# Margay.net
KiCad netlist of a schematic drawn in EAGLE
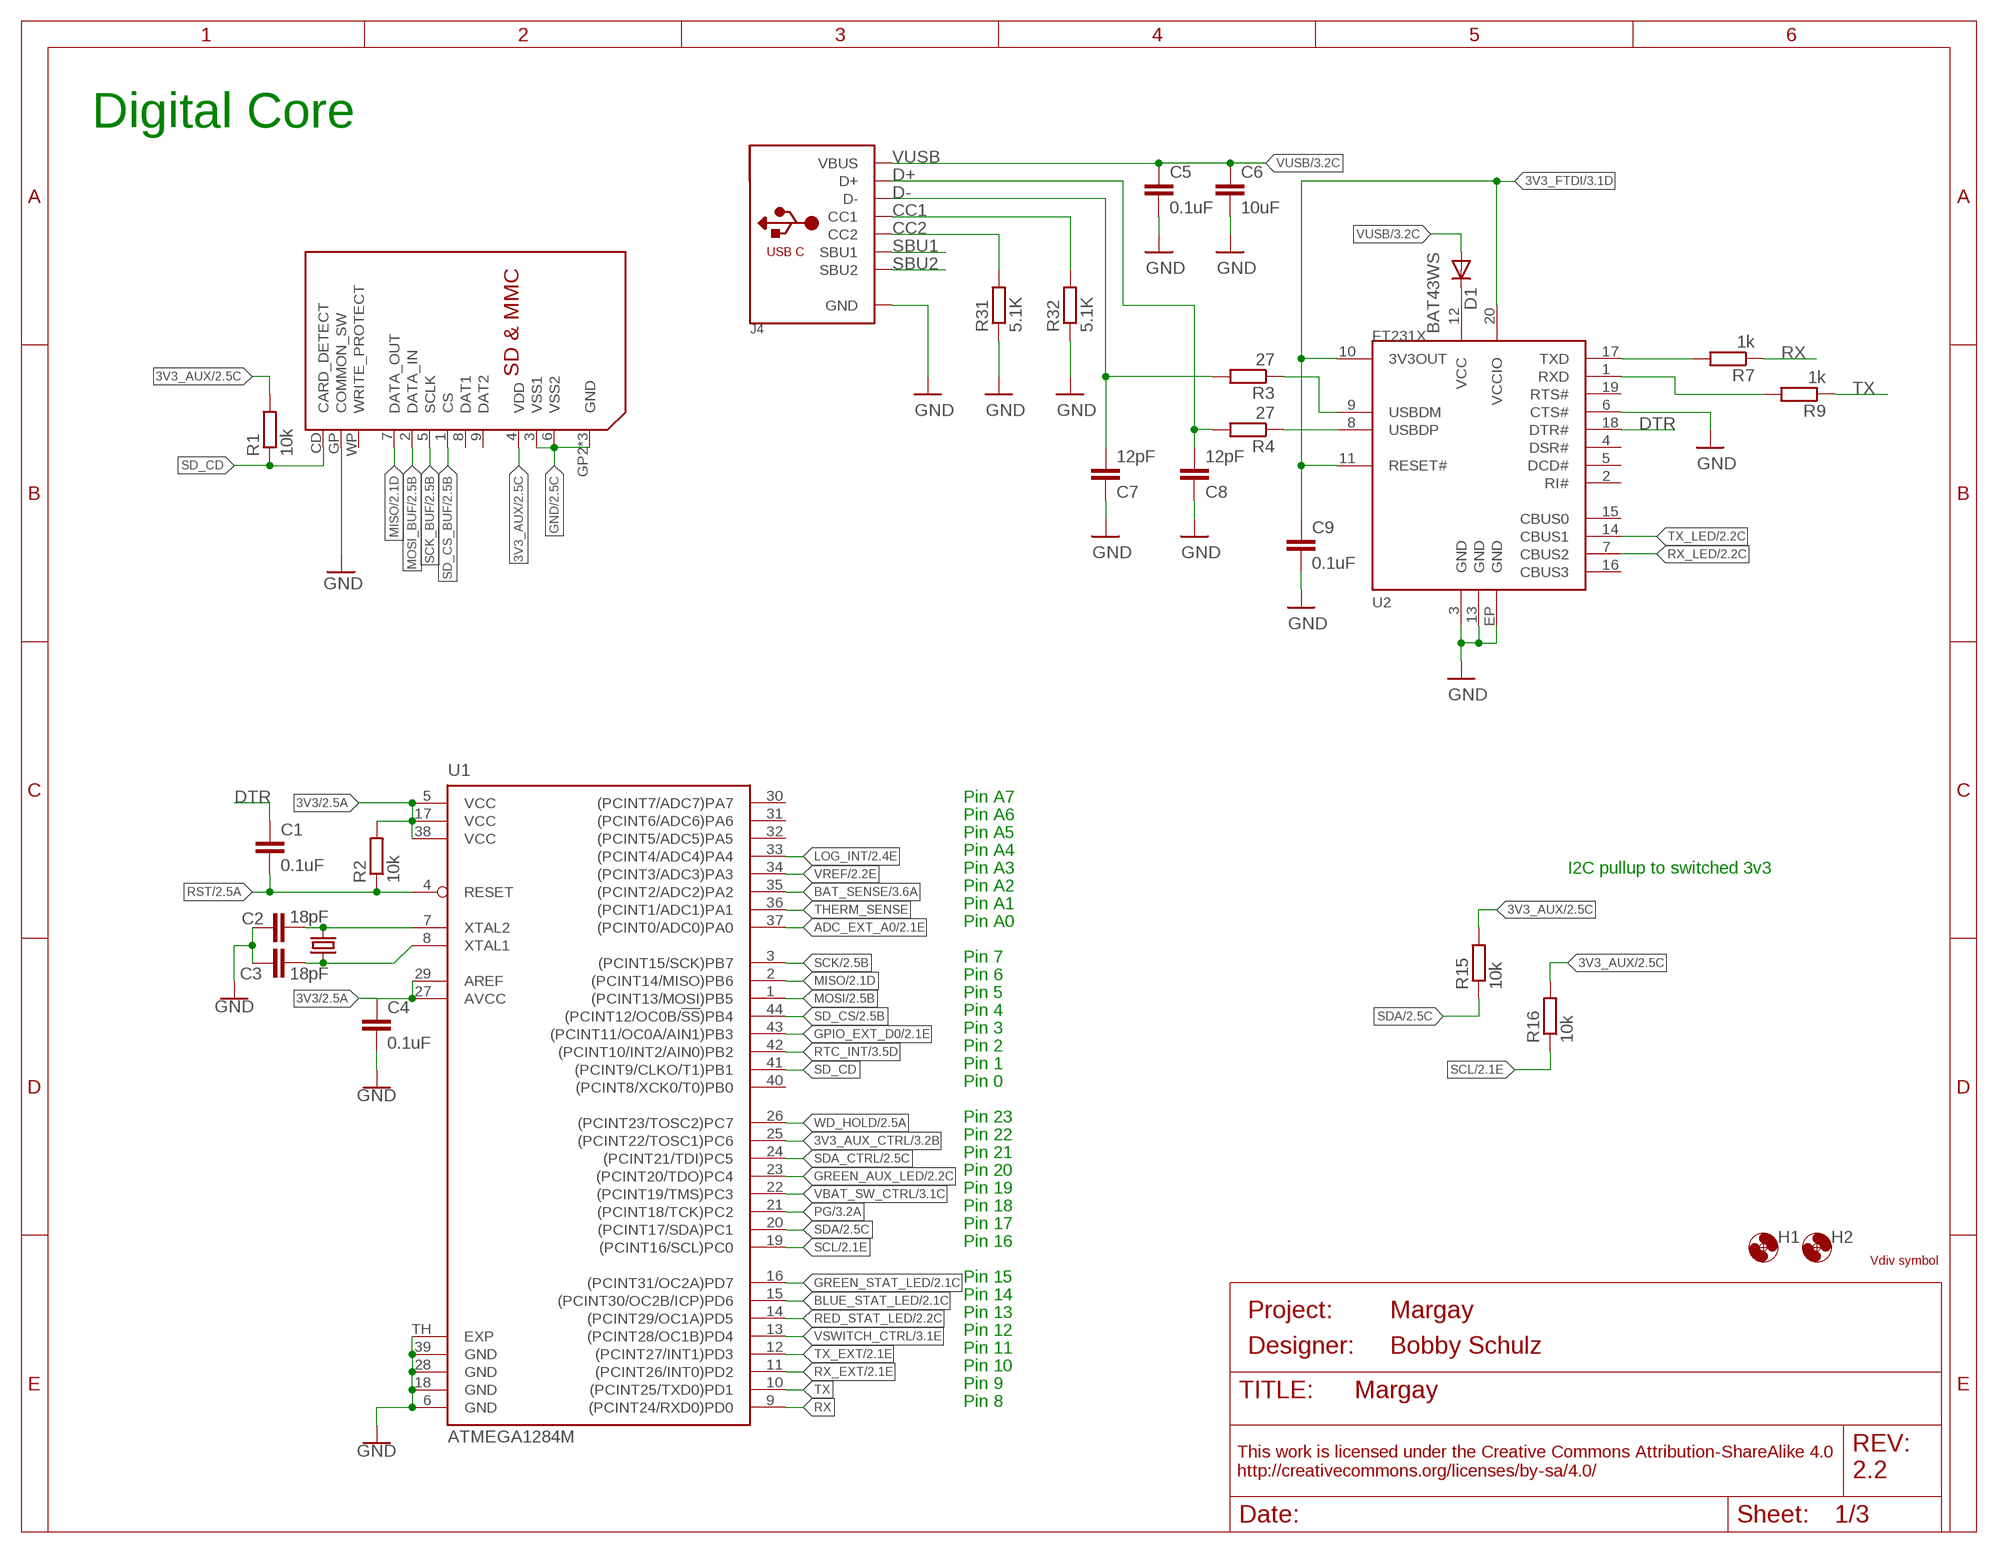
[diagram p0: schematic, sheet 1]
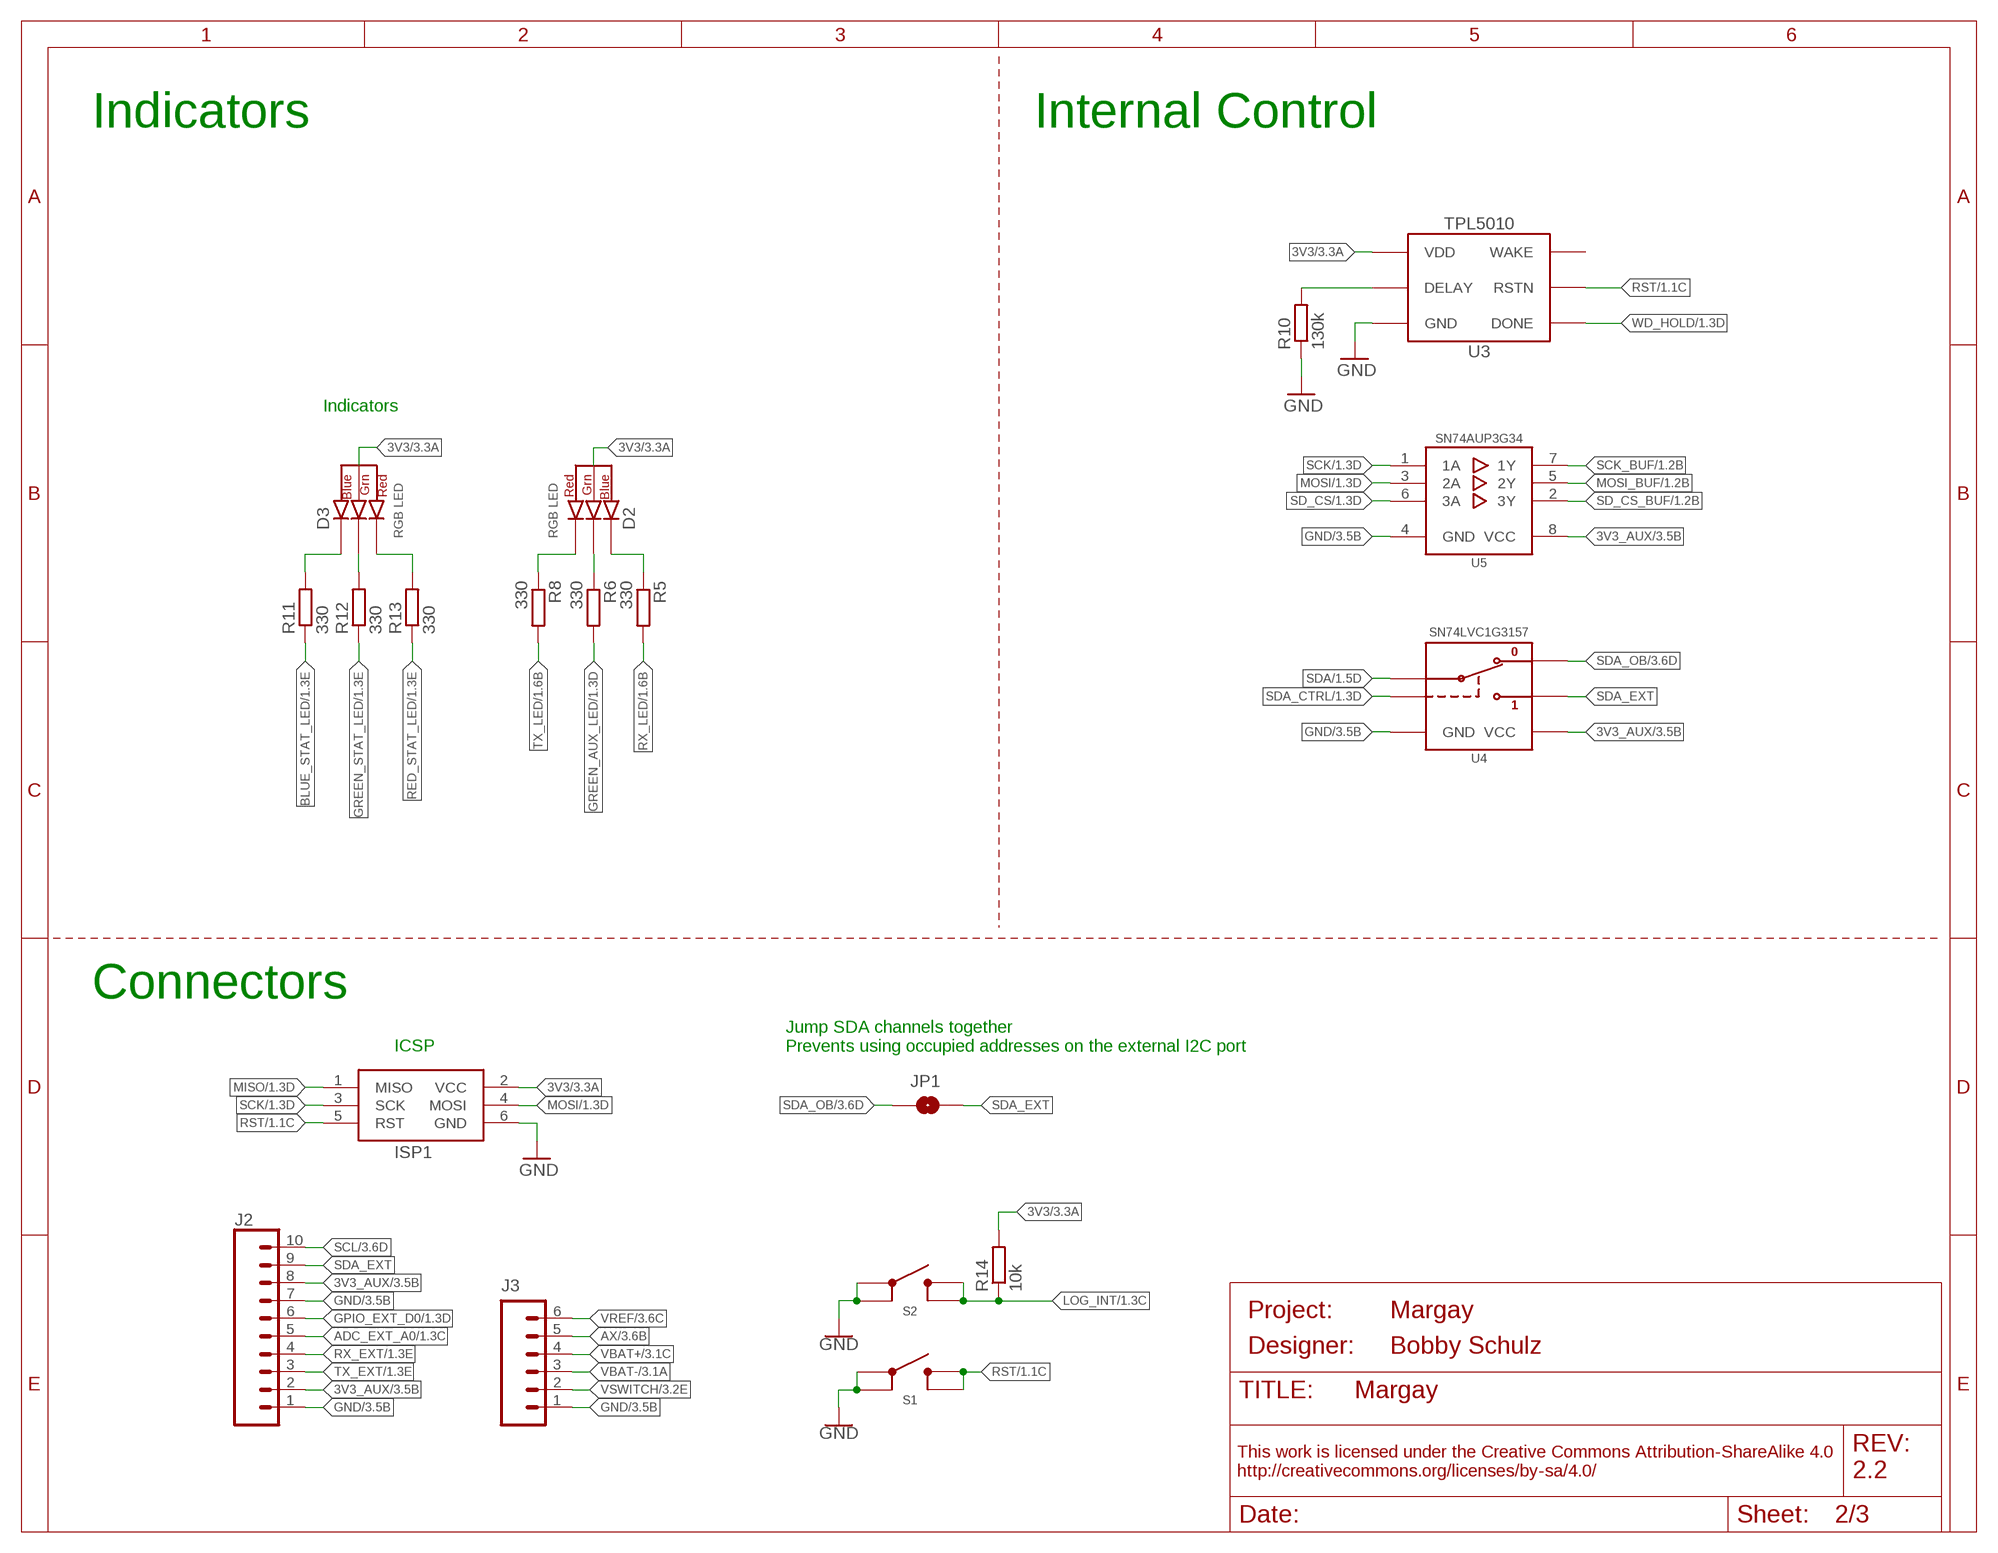
[diagram p1: schematic, sheet 2]
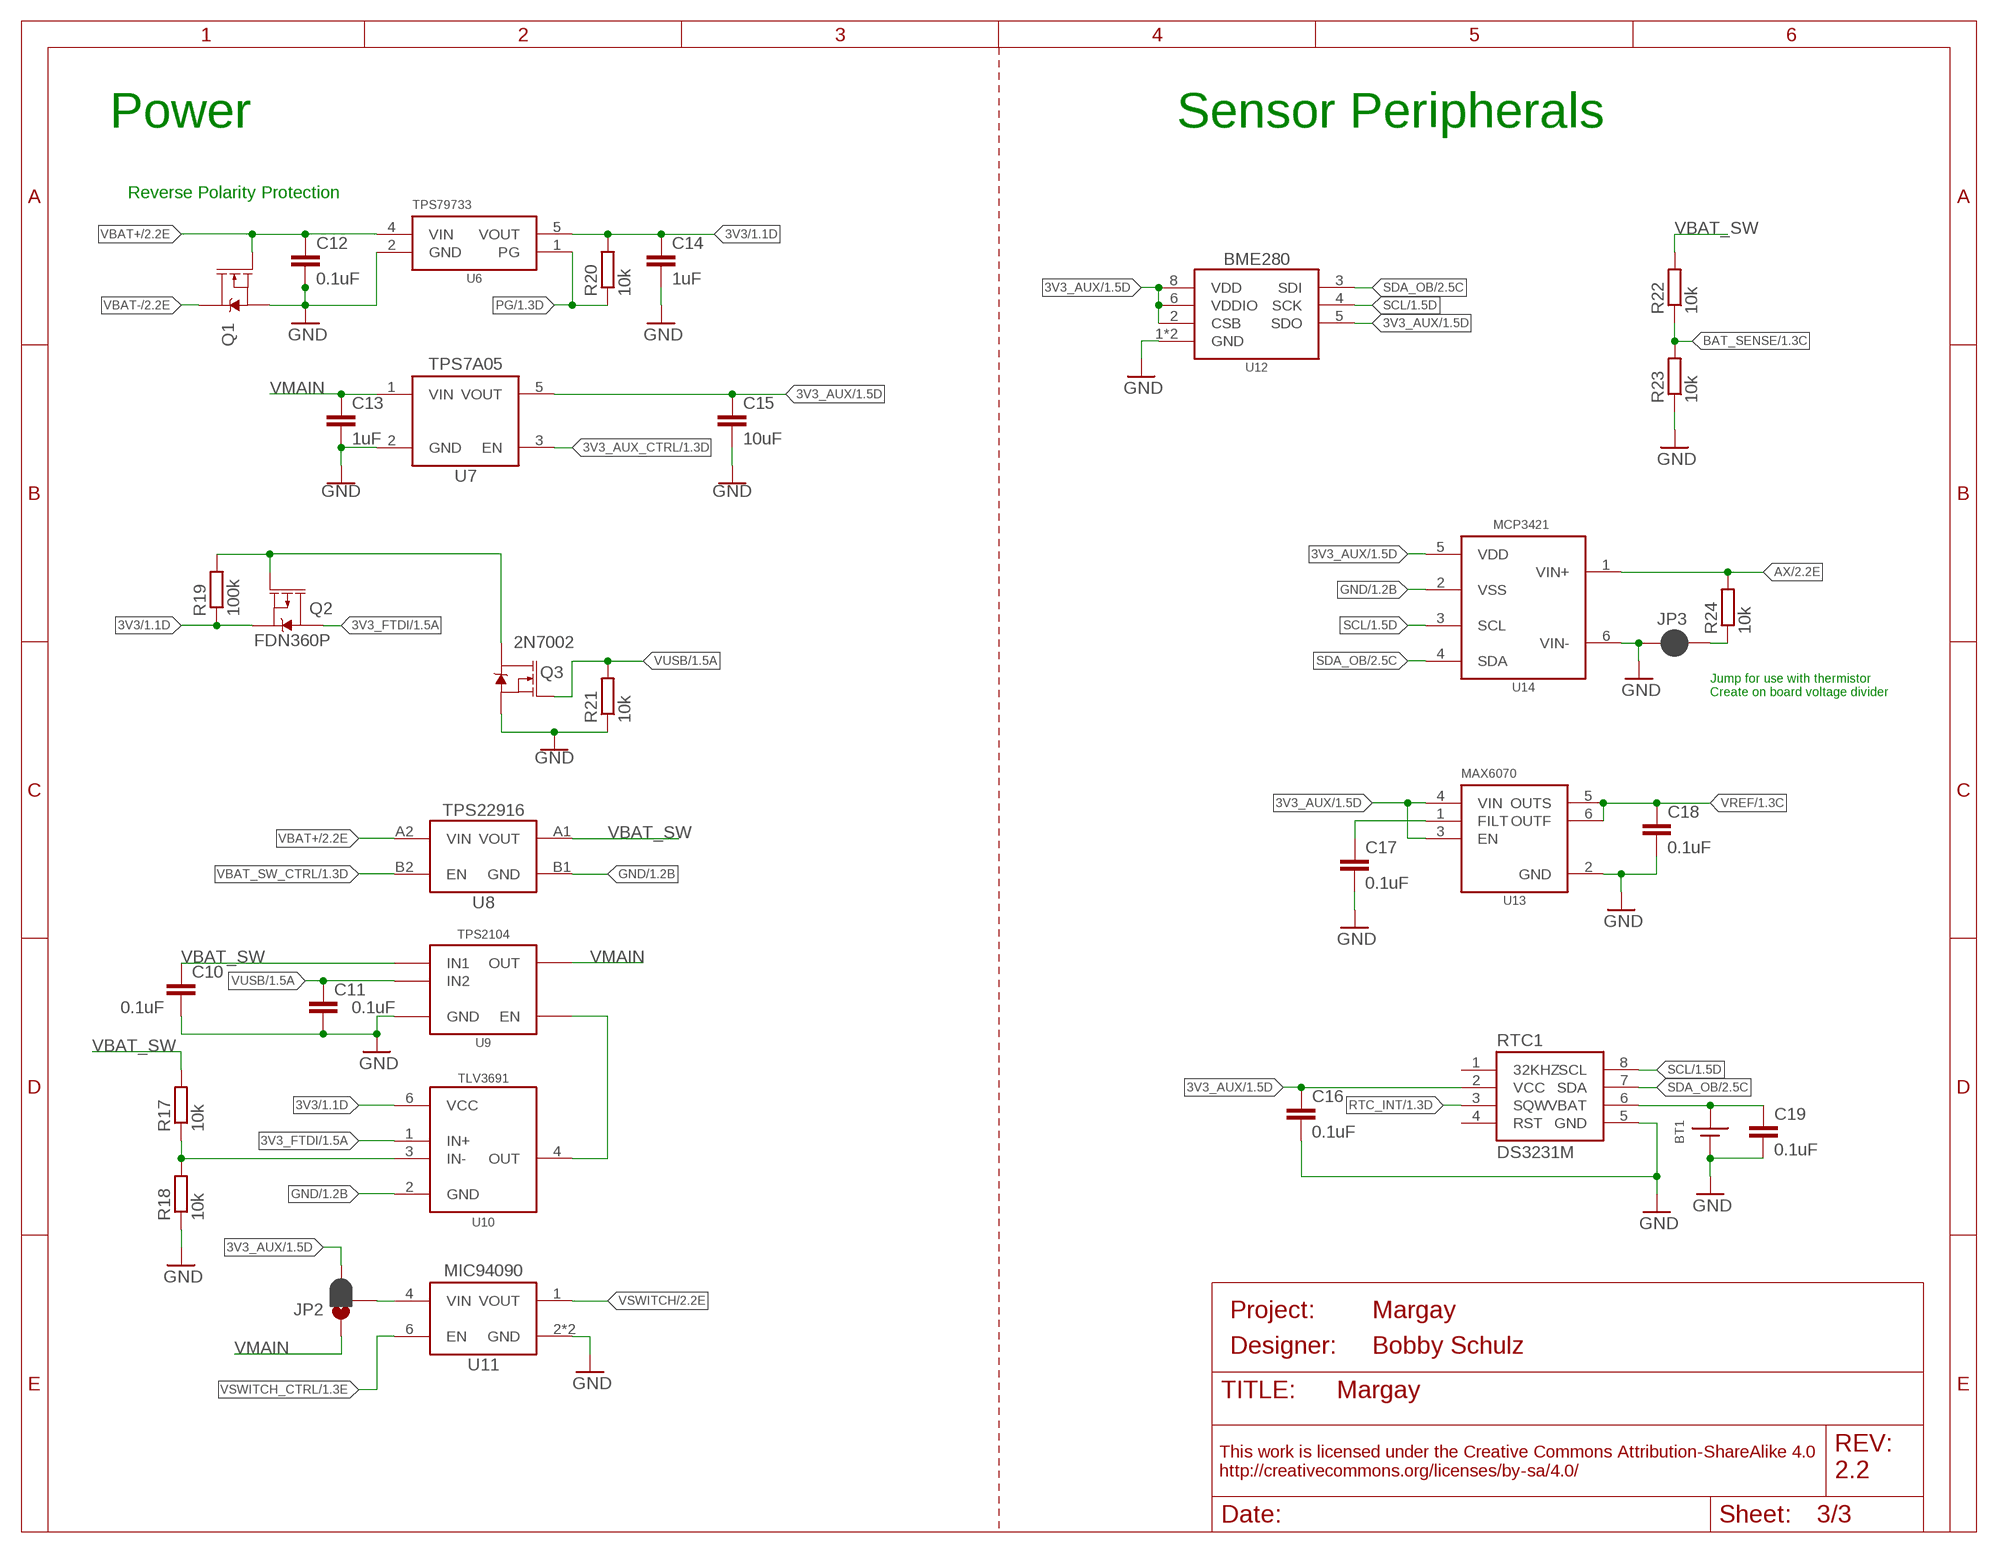
[diagram p2: schematic, sheet 3]

(export (version "E")
  (design (tool "Eeschema 10.0.6"))
  (components
    (comp (ref "D2")
      (value "CLVBA-FKA")
      (footprint "eagle-import:CLVBA-FKA")
      (fields (field (name "MF") "Cree") (field (name "MPN") "CLVBA-FKA-CAEDH8BBB7A363"))
      (libsource (lib "eagle-import") (part "CLVBA-FKA"))
    )
    (comp (ref "D3")
      (value "CLVBA-FKA")
      (footprint "eagle-import:CLVBA-FKA")
      (fields (field (name "MF") "Cree") (field (name "MPN") "CLVBA-FKA-CAEDH8BBB7A363"))
      (libsource (lib "eagle-import") (part "CLVBA-FKA"))
    )
    (comp (ref "ISP1")
      (value "AVRISP-6")
      (footprint "eagle-import:AVRISP")
      (fields (field (name "MF") "Amphenol") (field (name "MPN") "67997-206HLF"))
      (libsource (lib "eagle-import") (part "AVRISP-6"))
    )
    (comp (ref "J2")
      (value "CONN_102.54_SCREW")
      (footprint "eagle-import:1X10_SCREW")
      (fields (field (name "MF") "On Shore") (field (name "MPN") "OSTVN10A150"))
      (libsource (lib "eagle-import") (part "CONN_102.54_SCREW"))
    )
    (comp (ref "J3")
      (value "CONN_6SCREW_2.54")
      (footprint "eagle-import:1X06_SCREW")
      (fields (field (name "MF") "OnShore") (field (name "MPN") "OSTVN06A150"))
      (libsource (lib "eagle-import") (part "CONN_6SCREW_2.54"))
    )
    (comp (ref "JP1")
      (value "JUMPER-SMT_2_NO_SILK")
      (footprint "eagle-import:SMT-JUMPER_2_NO_SILK")
      (libsource (lib "eagle-import") (part "JUMPER-SMT_2_NO_SILK"))
    )
    (comp (ref "R5")
      (value "330")
      (footprint "eagle-import:R0402")
      (fields (field (name "MF") "Yageo") (field (name "MPN") "RC0402FR-07330RL"))
      (libsource (lib "eagle-import") (part "R-EU_R0402330"))
    )
    (comp (ref "R6")
      (value "330")
      (footprint "eagle-import:R0402")
      (fields (field (name "MF") "Yageo") (field (name "MPN") "RC0402FR-07330RL"))
      (libsource (lib "eagle-import") (part "R-EU_R0402330"))
    )
    (comp (ref "R8")
      (value "330")
      (footprint "eagle-import:R0402")
      (fields
        (field (name "MF") "Yageo")
        (field (name "MPN") "RC0402FR-07330RL")
        (field (name "MF_1") "Yageo")
      )
      (libsource (lib "eagle-import") (part "R-EU_R0402330"))
    )
    (comp (ref "R10")
      (value "130k")
      (footprint "eagle-import:R0603")
      (fields (field (name "MF") "Yageo") (field (name "MPN") "RC0603FR-07130KL"))
      (libsource (lib "eagle-import") (part "R-EU_R0603130K"))
    )
    (comp (ref "R11")
      (value "330")
      (footprint "eagle-import:R0402")
      (fields (field (name "MF") "Yageo") (field (name "MPN") "RC0402FR-07330RL"))
      (libsource (lib "eagle-import") (part "R-EU_R0402330"))
    )
    (comp (ref "R12")
      (value "330")
      (footprint "eagle-import:R0402")
      (fields (field (name "MF") "Yageo") (field (name "MPN") "RC0402FR-07330RL"))
      (libsource (lib "eagle-import") (part "R-EU_R0402330"))
    )
    (comp (ref "R13")
      (value "330")
      (footprint "eagle-import:R0402")
      (fields (field (name "MF") "Yageo") (field (name "MPN") "RC0402FR-07330RL"))
      (libsource (lib "eagle-import") (part "R-EU_R0402330"))
    )
    (comp (ref "R14")
      (value "10k")
      (footprint "eagle-import:R0402")
      (fields (field (name "MF") "Yageo") (field (name "MPN") "RC0402FR-0710KL"))
      (libsource (lib "eagle-import") (part "R-EU_R040210K"))
    )
    (comp (ref "S1")
      (value "BUTTON4.2X3.2")
      (footprint "eagle-import:SWITCH_4.2X3.2")
      (fields (field (name "MF") "C&K") (field (name "MPN") "PTS810 SJG 250 SMTR LFS"))
      (libsource (lib "eagle-import") (part "BUTTON4.2X3.2"))
    )
    (comp (ref "S2")
      (value "BUTTON4.2X3.2")
      (footprint "eagle-import:SWITCH_4.2X3.2")
      (fields (field (name "MF") "C&K") (field (name "MPN") "PTS810 SJG 250 SMTR LFS"))
      (libsource (lib "eagle-import") (part "BUTTON4.2X3.2"))
    )
    (comp (ref "U3")
      (value "TPL5010DDC")
      (footprint "eagle-import:DDC_R-PDSO-G6")
      (fields (field (name "MF") "TI") (field (name "MPN") "TPL5010DDCT"))
      (libsource (lib "eagle-import") (part "TPL5010DDC"))
    )
    (comp (ref "U4")
      (value "SN74LVC1G3157SC70")
      (footprint "eagle-import:DCK_R-PDSO-G6")
      (fields
        (field (name "DISP") "SN74LVC1G3157")
        (field (name "MF") "TI")
        (field (name "MPN") "SN74LVC1G3157DCKR")
      )
      (libsource (lib "eagle-import") (part "SN74LVC1G3157SC70"))
    )
    (comp (ref "U5")
      (value "SN74AUP3G34DCU")
      (footprint "eagle-import:DCU_(R-PDSO-G8)")
      (fields (field (name "MF") "TI") (field (name "MPN") "SN74AUP3G34DCUR"))
      (libsource (lib "eagle-import") (part "SN74AUP3G34DCU"))
    )
    (comp (ref "C1")
      (value "0.1uF")
      (footprint "eagle-import:C0402")
      (fields (field (name "MF") "Murata") (field (name "MPN") "GCM155R71C104KA55D"))
      (libsource (lib "eagle-import") (part "C-EUC04020.1UF"))
    )
    (comp (ref "C2")
      (value "18pF")
      (footprint "eagle-import:C0402")
      (fields (field (name "MF") "Murata") (field (name "MPN") "GCM1555C1H180JA16D"))
      (libsource (lib "eagle-import") (part "C-EUC040218PF"))
    )
    (comp (ref "C3")
      (value "18pF")
      (footprint "eagle-import:C0402")
      (fields (field (name "MF") "Murata") (field (name "MPN") "GCM1555C1H180JA16D"))
      (libsource (lib "eagle-import") (part "C-EUC040218PF"))
    )
    (comp (ref "C4")
      (value "0.1uF")
      (footprint "eagle-import:C0402")
      (fields (field (name "MF") "Murata") (field (name "MPN") "GCM155R71C104KA55D"))
      (libsource (lib "eagle-import") (part "C-EUC04020.1UF"))
    )
    (comp (ref "C5")
      (value "0.1uF")
      (footprint "eagle-import:C0402")
      (fields (field (name "MF") "Murata") (field (name "MPN") "GCM155R71C104KA55D"))
      (libsource (lib "eagle-import") (part "C-EUC04020.1UF"))
    )
    (comp (ref "C6")
      (value "10uF")
      (footprint "eagle-import:C0805")
      (fields (field (name "MF") "Murata") (field (name "MPN") "GRM21BR61C106KE15K"))
      (libsource (lib "eagle-import") (part "C-EUC080510UF"))
    )
    (comp (ref "C7")
      (value "12pF")
      (footprint "eagle-import:C0402")
      (fields (field (name "MF") "TDK") (field (name "MPN") "CGA2B2C0G1H120J050BA"))
      (libsource (lib "eagle-import") (part "C-EUC040212PF"))
    )
    (comp (ref "C8")
      (value "12pF")
      (footprint "eagle-import:C0402")
      (fields (field (name "MF") "TDK") (field (name "MPN") "CGA2B2C0G1H120J050BA"))
      (libsource (lib "eagle-import") (part "C-EUC040212PF"))
    )
    (comp (ref "C9")
      (value "0.1uF")
      (footprint "eagle-import:C0402")
      (fields (field (name "MF") "Murata") (field (name "MPN") "GCM155R71C104KA55D"))
      (libsource (lib "eagle-import") (part "C-EUC04020.1UF"))
    )
    (comp (ref "D1")
      (value "BAT43WS")
      (footprint "eagle-import:SOD323-R")
      (fields
        (field (name "DIGIKEY") "BAT43WS-FDICT-ND")
        (field (name "MF") "Diodes Incorporated")
        (field (name "MPN") "BAT43WS-7-F")
      )
      (libsource (lib "eagle-import") (part "DIODESOD-323"))
    )
    (comp (ref "H1")
      (value "MOUNTING_HOLE4_NP_CLOSE")
      (footprint "eagle-import:4_40_CLOSE")
      (libsource (lib "eagle-import") (part "MOUNTING_HOLE4_NP_CLOSE"))
    )
    (comp (ref "H2")
      (value "MOUNTING_HOLE4_NP_CLOSE")
      (footprint "eagle-import:4_40_CLOSE")
      (libsource (lib "eagle-import") (part "MOUNTING_HOLE4_NP_CLOSE"))
    )
    (comp (ref "J1")
      (value "SDMMCWR-CRD")
      (footprint "eagle-import:SD_WURTH_WR-CRD")
      (fields (field (name "MF") "Wurth") (field (name "MPN") "693063010911"))
      (libsource (lib "eagle-import") (part "SDMMCWR-CRD"))
    )
    (comp (ref "J4")
      (value "USB_C")
      (footprint "eagle-import:USB_C_CUSB31-CFM2AX-01-X")
      (fields (field (name "MF") "GCT") (field (name "MPN") "USB4105-GF-A"))
      (libsource (lib "eagle-import") (part "USB_C"))
    )
    (comp (ref "R1")
      (value "10k")
      (footprint "eagle-import:R0402")
      (fields (field (name "MF") "Yageo") (field (name "MPN") "RC0402FR-0710KL"))
      (libsource (lib "eagle-import") (part "R-EU_R040210K"))
    )
    (comp (ref "R2")
      (value "10k")
      (footprint "eagle-import:R0402")
      (fields (field (name "MF") "Yageo") (field (name "MPN") "RC0402FR-0710KL"))
      (libsource (lib "eagle-import") (part "R-EU_R040210K"))
    )
    (comp (ref "R3")
      (value "27")
      (footprint "eagle-import:R0402")
      (fields (field (name "MF") "Yageo") (field (name "MPN") "RC0402FR-0727RL"))
      (libsource (lib "eagle-import") (part "R-EU_R040227"))
    )
    (comp (ref "R4")
      (value "27")
      (footprint "eagle-import:R0402")
      (fields (field (name "MF") "Yageo") (field (name "MPN") "RC0402FR-0727RL"))
      (libsource (lib "eagle-import") (part "R-EU_R040227"))
    )
    (comp (ref "R7")
      (value "1k")
      (footprint "eagle-import:R0402")
      (fields
        (field (name "MF") "Yageo")
        (field (name "MPN") "RC0402FR-071KL")
        (field (name "MPN_1") "RC0603FR-07330RL")
      )
      (libsource (lib "eagle-import") (part "R-EU_R04021K"))
    )
    (comp (ref "R9")
      (value "1k")
      (footprint "eagle-import:R0402")
      (fields
        (field (name "MF") "Yageo")
        (field (name "MPN") "RC0402FR-071KL")
        (field (name "MPN_1") "RC0603FR-07330RL")
      )
      (libsource (lib "eagle-import") (part "R-EU_R04021K"))
    )
    (comp (ref "R15")
      (value "10k")
      (footprint "eagle-import:R0402")
      (fields (field (name "MF") "Yageo") (field (name "MPN") "RC0402FR-0710KL"))
      (libsource (lib "eagle-import") (part "R-EU_R040210K"))
    )
    (comp (ref "R16")
      (value "10k")
      (footprint "eagle-import:R0402")
      (fields (field (name "MF") "Yageo") (field (name "MPN") "RC0402FR-0710KL"))
      (libsource (lib "eagle-import") (part "R-EU_R040210K"))
    )
    (comp (ref "R31")
      (value "5.1K")
      (footprint "eagle-import:R0402")
      (fields
        (field (name "MF") "Yageo")
        (field (name "MPN") "RC0402FR-075K1L")
        (field (name "VALUE_PART") "5.1k")
      )
      (libsource (lib "eagle-import") (part "R-EU_R04025.1K"))
    )
    (comp (ref "R32")
      (value "5.1K")
      (footprint "eagle-import:R0402")
      (fields
        (field (name "MF") "Yageo")
        (field (name "MPN") "RC0402FR-075K1L")
        (field (name "VALUE_PART") "5.1k")
      )
      (libsource (lib "eagle-import") (part "R-EU_R04025.1K"))
    )
    (comp (ref "U$1")
      (value "VDIV_MARGAYFULL-VDIV")
      (footprint "eagle-import:VDIV_MARGAY_2021")
      (libsource (lib "eagle-import") (part "VDIV_MARGAYFULL-VDIV"))
    )
    (comp (ref "U1")
      (value "ATMEGA1284M")
      (footprint "eagle-import:MLF44-TH")
      (fields (field (name "MF") "Atmel") (field (name "MPN") "ATMEGA1284P-MUR"))
      (libsource (lib "eagle-import") (part "ATMEGA1284M"))
    )
    (comp (ref "U2")
      (value "FT231X-Q")
      (footprint "eagle-import:QFN20")
      (fields (field (name "MF") "FTDI") (field (name "MPN") "FT231XQ-R"))
      (libsource (lib "eagle-import") (part "FT231X-Q"))
    )
    (comp (ref "XTAL1")
      (value "CRYSTAL8MHZ5X3.2")
      (footprint "eagle-import:CRYSTAL_5X3.2_2-SMD")
      (fields
        (field (name "MF") "TXC")
        (field (name "MPN") "7A-8.000MAAE-T")
        (field (name "DIGIKEY") "XC2103CT-ND")
        (field (name "MF_1") "ECS")
        (field (name "MPN_1") "ECS-80-18-30-JGN-TR")
      )
      (libsource (lib "eagle-import") (part "CRYSTAL5X3.28MHZ"))
    )
    (comp (ref "BT1")
      (value "BATTERY_COIN12MM")
      (footprint "eagle-import:LINX_BAT-HLD-012-SMT")
      (fields (field (name "MF") "Linx") (field (name "MPN") "BAT-HLD-012-SMT"))
      (libsource (lib "eagle-import") (part "BATTERY_COIN12MM"))
    )
    (comp (ref "C10")
      (value "0.1uF")
      (footprint "eagle-import:C0402")
      (fields (field (name "MF") "Murata") (field (name "MPN") "GCM155R71C104KA55D"))
      (libsource (lib "eagle-import") (part "C-EUC04020.1UF"))
    )
    (comp (ref "C11")
      (value "0.1uF")
      (footprint "eagle-import:C0402")
      (fields (field (name "MF") "Murata") (field (name "MPN") "GCM155R71C104KA55D"))
      (libsource (lib "eagle-import") (part "C-EUC04020.1UF"))
    )
    (comp (ref "C12")
      (value "0.1uF")
      (footprint "eagle-import:C0402")
      (fields (field (name "MF") "Murata") (field (name "MPN") "GCM155R71C104KA55D"))
      (libsource (lib "eagle-import") (part "C-EUC04020.1UF"))
    )
    (comp (ref "C13")
      (value "1uF")
      (footprint "eagle-import:C0603")
      (fields (field (name "MF") "Yaiyo Yuden") (field (name "MPN") "TMK107B7105KA-T"))
      (libsource (lib "eagle-import") (part "C-EUC06031UF"))
    )
    (comp (ref "C14")
      (value "1uF")
      (footprint "eagle-import:C0603")
      (fields (field (name "MF") "Yaiyo Yuden") (field (name "MPN") "TMK107B7105KA-T"))
      (libsource (lib "eagle-import") (part "C-EUC06031UF"))
    )
    (comp (ref "C15")
      (value "10uF")
      (footprint "eagle-import:C0805")
      (fields (field (name "MF") "Murata") (field (name "MPN") "GRM21BR61C106KE15K"))
      (libsource (lib "eagle-import") (part "C-EUC080510UF"))
    )
    (comp (ref "C16")
      (value "0.1uF")
      (footprint "eagle-import:C0402")
      (fields (field (name "MF") "Murata") (field (name "MPN") "GCM155R71C104KA55D"))
      (libsource (lib "eagle-import") (part "C-EUC04020.1UF"))
    )
    (comp (ref "C17")
      (value "0.1uF")
      (footprint "eagle-import:C0402")
      (fields (field (name "MF") "Murata") (field (name "MPN") "GCM155R71C104KA55D"))
      (libsource (lib "eagle-import") (part "C-EUC04020.1UF"))
    )
    (comp (ref "C18")
      (value "0.1uF")
      (footprint "eagle-import:C0402")
      (fields (field (name "MF") "Murata") (field (name "MPN") "GCM155R71C104KA55D"))
      (libsource (lib "eagle-import") (part "C-EUC04020.1UF"))
    )
    (comp (ref "C19")
      (value "0.1uF")
      (footprint "eagle-import:C0402")
      (fields (field (name "MF") "Murata") (field (name "MPN") "GCM155R71C104KA55D"))
      (libsource (lib "eagle-import") (part "C-EUC04020.1UF"))
    )
    (comp (ref "JP2")
      (value "JUMPER-SMT_3_1-NC_PASTE_SILK")
      (footprint "eagle-import:SMT-JUMPER_3_1-NC_PASTE_SILK")
      (libsource (lib "eagle-import") (part "JUMPER-SMT_3_1-NC_PASTE_SILK"))
    )
    (comp (ref "JP3")
      (value "JUMPER-SMT_2_NC_PASTE_SILK")
      (footprint "eagle-import:SMT-JUMPER_2_NC_PASTE_SILK")
      (libsource (lib "eagle-import") (part "JUMPER-SMT_2_NC_PASTE_SILK"))
    )
    (comp (ref "Q1")
      (value "DMG3404")
      (footprint "eagle-import:SOT23-3")
      (fields (field (name "MF") "Diodes Incorporated") (field (name "MPN") "DMG3404L-7"))
      (libsource (lib "eagle-import") (part "MOSFET-NCH-DMG3404L"))
    )
    (comp (ref "Q2")
      (value "FDN360P")
      (footprint "eagle-import:SOT23-3@1")
      (fields
        (field (name "MF") "Fairchild")
        (field (name "DIGIKEY") "DMP3099L-7DICT-ND")
        (field (name "MF_1") "Diodes Inc")
        (field (name "MPN") "DMP3099L-7")
      )
      (libsource (lib "eagle-import") (part "MOSFET_PCH-FDN360P"))
    )
    (comp (ref "Q3")
      (value "2N7002")
      (footprint "eagle-import:SOT323")
      (fields (field (name "MF") "Diodes Incorporated") (field (name "MPN") "2N7002W-7-F"))
      (libsource (lib "eagle-import") (part "MOSFET-NCH-2N7002PW"))
    )
    (comp (ref "R17")
      (value "10k")
      (footprint "eagle-import:R0402")
      (fields (field (name "MF") "Yageo") (field (name "MPN") "RC0402FR-0710KL"))
      (libsource (lib "eagle-import") (part "R-EU_R040210K"))
    )
    (comp (ref "R18")
      (value "10k")
      (footprint "eagle-import:R0402")
      (fields (field (name "MF") "Yageo") (field (name "MPN") "RC0402FR-0710KL"))
      (libsource (lib "eagle-import") (part "R-EU_R040210K"))
    )
    (comp (ref "R19")
      (value "100k")
      (footprint "eagle-import:R0402")
      (fields
        (field (name "MF") "Yageo")
        (field (name "MPN") "RC0402FR-07100RL")
        (field (name "VALUE_PART") "100")
      )
      (libsource (lib "eagle-import") (part "R-EU_R0402100"))
    )
    (comp (ref "R20")
      (value "10k")
      (footprint "eagle-import:R0402")
      (fields (field (name "MF") "Yageo") (field (name "MPN") "RC0402FR-0710KL"))
      (libsource (lib "eagle-import") (part "R-EU_R040210K"))
    )
    (comp (ref "R21")
      (value "10k")
      (footprint "eagle-import:R0402")
      (fields (field (name "MF") "Yageo") (field (name "MPN") "RC0402FR-0710KL"))
      (libsource (lib "eagle-import") (part "R-EU_R040210K"))
    )
    (comp (ref "R22")
      (value "10k")
      (footprint "eagle-import:R0603")
      (fields (field (name "MF") "Yageo") (field (name "MPN") "RC0603FR-0710KL"))
      (libsource (lib "eagle-import") (part "R-EU_R060310K"))
    )
    (comp (ref "R23")
      (value "10k")
      (footprint "eagle-import:R0603")
      (fields (field (name "MF") "Yageo") (field (name "MPN") "RC0603FR-0710KL"))
      (libsource (lib "eagle-import") (part "R-EU_R060310K"))
    )
    (comp (ref "R24")
      (value "10k")
      (footprint "eagle-import:R0603")
      (fields
        (field (name "MF") "Panasonic")
        (field (name "MPN") "ERA-3AEB103V")
        (field (name "DIGIKEY") "CRT0603-BY-1002ELFCT-ND")
        (field (name "MF_1") "Bourns")
        (field (name "MPN_1") "CRT0603-BY-1002ELF")
      )
      (libsource (lib "eagle-import") (part "R-EU_R0603P10K"))
    )
    (comp (ref "RTC1")
      (value "DS3231M")
      (footprint "eagle-import:SO08")
      (fields (field (name "MF") "Maxim") (field (name "MPN") "DS3231MZ+"))
      (libsource (lib "eagle-import") (part "DS3231M"))
    )
    (comp (ref "U6")
      (value "TPS79733")
      (footprint "eagle-import:DCK_R-PDSO-G5")
      (fields (field (name "DISP") "TPS79733") (field (name "MF") "TI") (field (name "MPN") "TPS79733DCKR"))
      (libsource (lib "eagle-import") (part "TPS79733"))
    )
    (comp (ref "U7")
      (value "TPS7A0533DBV")
      (footprint "eagle-import:SOT23-5")
      (fields (field (name "MF") "TI") (field (name "MPN") "TPS7A0533PDBVR"))
      (libsource (lib "eagle-import") (part "TPS7A05DBV33"))
    )
    (comp (ref "U8")
      (value "TPS22916YFP")
      (footprint "eagle-import:YFP0004")
      (fields (field (name "MF") "TI") (field (name "MPN") "TPS22916CYFPT"))
      (libsource (lib "eagle-import") (part "TPS22916YFP"))
    )
    (comp (ref "U9")
      (value "TPS2104")
      (footprint "eagle-import:SOT23-5")
      (fields
        (field (name "DISP") "TPS2104")
        (field (name "MF") "TI")
        (field (name "MPN") "TPS2104DBVR")
        (field (name "DIGIKEY") "296-TPS2104DBVTCT-ND")
        (field (name "MPN_1") "TPS2104DBVT")
      )
      (libsource (lib "eagle-import") (part "TPS2104"))
    )
    (comp (ref "U10")
      (value "TLV3691DPF")
      (footprint "eagle-import:DPF0006A")
      (fields (field (name "MF") "TI") (field (name "MPN") "TLV3691IDPFR"))
      (libsource (lib "eagle-import") (part "TLV3691DPF"))
    )
    (comp (ref "U11")
      (value "MIC94090C6")
      (footprint "eagle-import:SC-70_6")
      (fields
        (field (name "DISP") "MIC94090")
        (field (name "MF") "Microchip")
        (field (name "MPN") "MIC94090YC6-TR")
      )
      (libsource (lib "eagle-import") (part "MIC9409C60"))
    )
    (comp (ref "U12")
      (value "BME280")
      (footprint "eagle-import:BME280")
      (fields (field (name "DISP") "BME280") (field (name "MF") "Bosch"))
      (libsource (lib "eagle-import") (part "BME280"))
    )
    (comp (ref "U13")
      (value "MAX6070AAUT18")
      (footprint "eagle-import:SOT23-6L")
      (fields
        (field (name "MF") "Maxim")
        (field (name "MPN") "MAX6070BAUT18+T")
        (field (name "DIGIKEY") "MAX6071AAUT18+TCT-ND")
        (field (name "MPN_1") "MAX6071AAUT18+T")
      )
      (libsource (lib "eagle-import") (part "MAX6070AAUT18"))
    )
    (comp (ref "U14")
      (value "MCP3421A1")
      (footprint "eagle-import:SOT23-6L")
      (fields
        (field (name "DISP") "MCP3421")
        (field (name "MF") "Microchip")
        (field (name "MPN") "MCP3421A1T-E/CH")
      )
      (libsource (lib "eagle-import") (part "MCP3421A1"))
    )
  )
  (nets
    (net (code "1") (name "3V3") (class "Default")
      (node (ref "C14") (pin "1") (pinfunction "1_1") (pintype "passive"))
      (node (ref "C4") (pin "1") (pinfunction "1_1") (pintype "passive"))
      (node (ref "D2") (pin "2") (pinfunction "ANODE_2") (pintype "bidirectional"))
      (node (ref "D3") (pin "2") (pinfunction "ANODE_2") (pintype "bidirectional"))
      (node (ref "ISP1") (pin "2") (pinfunction "VCC_2") (pintype "power_in"))
      (node (ref "Q2") (pin "2") (pinfunction "S_2") (pintype "bidirectional"))
      (node (ref "R14") (pin "2") (pinfunction "2_2") (pintype "passive"))
      (node (ref "R19") (pin "1") (pinfunction "1_1") (pintype "passive"))
      (node (ref "R2") (pin "2") (pinfunction "2_2") (pintype "passive"))
      (node (ref "R20") (pin "2") (pinfunction "2_2") (pintype "passive"))
      (node (ref "U1") (pin "17") (pinfunction "VCC_17") (pintype "power_in"))
      (node (ref "U1") (pin "27") (pinfunction "AVCC_27") (pintype "power_in"))
      (node (ref "U1") (pin "29") (pinfunction "AREF_29") (pintype "passive"))
      (node (ref "U1") (pin "38") (pinfunction "VCC_38") (pintype "power_in"))
      (node (ref "U1") (pin "5") (pinfunction "VCC_5") (pintype "power_in"))
      (node (ref "U10") (pin "6") (pinfunction "VCC_6") (pintype "power_in"))
      (node (ref "U3") (pin "1") (pinfunction "VDD_1") (pintype "power_in"))
      (node (ref "U6") (pin "5") (pinfunction "VOUT_5") (pintype "bidirectional"))
    )
    (net (code "2") (name "3V3_AUX") (class "Default")
      (node (ref "C15") (pin "1") (pinfunction "1_1") (pintype "passive"))
      (node (ref "C16") (pin "1") (pinfunction "1_1") (pintype "passive"))
      (node (ref "J1") (pin "4") (pinfunction "VDD_4") (pintype "power_in"))
      (node (ref "J2") (pin "2") (pinfunction "2_2") (pintype "passive"))
      (node (ref "J2") (pin "8") (pinfunction "8_8") (pintype "passive"))
      (node (ref "JP2") (pin "3") (pinfunction "3_3") (pintype "passive"))
      (node (ref "R1") (pin "2") (pinfunction "2_2") (pintype "passive"))
      (node (ref "R15") (pin "2") (pinfunction "2_2") (pintype "passive"))
      (node (ref "R16") (pin "2") (pinfunction "2_2") (pintype "passive"))
      (node (ref "RTC1") (pin "2") (pinfunction "VCC_2") (pintype "power_in"))
      (node (ref "U12") (pin "2") (pinfunction "CSB_2") (pintype "bidirectional"))
      (node (ref "U12") (pin "5") (pinfunction "SDO_5") (pintype "bidirectional"))
      (node (ref "U12") (pin "6") (pinfunction "VDDIO_6") (pintype "bidirectional"))
      (node (ref "U12") (pin "8") (pinfunction "VDD_8") (pintype "power_in"))
      (node (ref "U13") (pin "3") (pinfunction "EN_3") (pintype "bidirectional"))
      (node (ref "U13") (pin "4") (pinfunction "VIN_4") (pintype "bidirectional"))
      (node (ref "U14") (pin "5") (pinfunction "VDD_5") (pintype "passive"))
      (node (ref "U4") (pin "5") (pinfunction "VCC_5") (pintype "power_in"))
      (node (ref "U5") (pin "8") (pinfunction "VCC_8") (pintype "power_in"))
      (node (ref "U7") (pin "5") (pinfunction "VOUT_5") (pintype "power_in"))
    )
    (net (code "3") (name "3V3_AUX_CTRL") (class "Default")
      (node (ref "U1") (pin "25") (pinfunction "(PCINT22/TOSC1)PC6_25") (pintype "output"))
      (node (ref "U7") (pin "3") (pinfunction "EN_3") (pintype "input"))
    )
    (net (code "4") (name "3V3_FTDI") (class "Default")
      (node (ref "C9") (pin "1") (pinfunction "1_1") (pintype "passive"))
      (node (ref "Q2") (pin "3") (pinfunction "D_3") (pintype "bidirectional"))
      (node (ref "U10") (pin "1") (pinfunction "IN+_1") (pintype "input"))
      (node (ref "U2") (pin "10") (pinfunction "3V3OUT_10") (pintype "bidirectional"))
      (node (ref "U2") (pin "11") (pinfunction "RESET#_11") (pintype "bidirectional"))
      (node (ref "U2") (pin "20") (pinfunction "VCCIO_20") (pintype "bidirectional"))
    )
    (net (code "5") (name "ADC_EXT_A0") (class "Default")
      (node (ref "J2") (pin "5") (pinfunction "5_5") (pintype "passive"))
      (node (ref "U1") (pin "37") (pinfunction "(PCINT0/ADC0)PA0_37") (pintype "bidirectional"))
    )
    (net (code "6") (name "AX") (class "Default")
      (node (ref "J3") (pin "5") (pinfunction "5_5") (pintype "passive"))
      (node (ref "R24") (pin "2") (pinfunction "2_2") (pintype "passive"))
      (node (ref "U14") (pin "1") (pinfunction "VIN+_1") (pintype "input"))
    )
    (net (code "7") (name "BAT_SENSE") (class "Default")
      (node (ref "R22") (pin "1") (pinfunction "1_1") (pintype "passive"))
      (node (ref "R23") (pin "2") (pinfunction "2_2") (pintype "passive"))
      (node (ref "U1") (pin "35") (pinfunction "(PCINT2/ADC2)PA2_35") (pintype "bidirectional"))
    )
    (net (code "8") (name "BLUE_STAT_LED") (class "Default")
      (node (ref "R11") (pin "1") (pinfunction "1_1") (pintype "passive"))
      (node (ref "U1") (pin "15") (pinfunction "(PCINT30/OC2B/ICP)PD6_15") (pintype "bidirectional"))
    )
    (net (code "9") (name "CC1") (class "Default")
      (node (ref "J4") (pin "A5") (pinfunction "CC1_A5") (pintype "bidirectional"))
      (node (ref "R32") (pin "2") (pinfunction "2_2") (pintype "passive"))
    )
    (net (code "10") (name "CC2") (class "Default")
      (node (ref "J4") (pin "B5") (pinfunction "CC2_B5") (pintype "bidirectional"))
      (node (ref "R31") (pin "2") (pinfunction "2_2") (pintype "passive"))
    )
    (net (code "11") (name "D+") (class "Default")
      (node (ref "C8") (pin "2") (pinfunction "2_2") (pintype "passive"))
      (node (ref "J4") (pin "A6") (pinfunction "D+_A6") (pintype "bidirectional"))
      (node (ref "J4") (pin "B6") (pinfunction "D+_B6") (pintype "bidirectional"))
      (node (ref "R4") (pin "2") (pinfunction "2_2") (pintype "passive"))
    )
    (net (code "12") (name "D-") (class "Default")
      (node (ref "C7") (pin "2") (pinfunction "2_2") (pintype "passive"))
      (node (ref "J4") (pin "A7") (pinfunction "D-_A7") (pintype "bidirectional"))
      (node (ref "J4") (pin "B7") (pinfunction "D-_B7") (pintype "bidirectional"))
      (node (ref "R3") (pin "2") (pinfunction "2_2") (pintype "passive"))
    )
    (net (code "13") (name "DTR") (class "Default")
      (node (ref "C1") (pin "1") (pinfunction "1_1") (pintype "passive"))
      (node (ref "U2") (pin "18") (pinfunction "DTR#_18") (pintype "bidirectional"))
    )
    (net (code "14") (name "GND") (class "Default")
      (node (ref "BT1") (pin "GND") (pinfunction "-_GND") (pintype "power_in"))
      (node (ref "C10") (pin "2") (pinfunction "2_2") (pintype "passive"))
      (node (ref "C11") (pin "2") (pinfunction "2_2") (pintype "passive"))
      (node (ref "C12") (pin "2") (pinfunction "2_2") (pintype "passive"))
      (node (ref "C13") (pin "2") (pinfunction "2_2") (pintype "passive"))
      (node (ref "C14") (pin "2") (pinfunction "2_2") (pintype "passive"))
      (node (ref "C15") (pin "2") (pinfunction "2_2") (pintype "passive"))
      (node (ref "C16") (pin "2") (pinfunction "2_2") (pintype "passive"))
      (node (ref "C17") (pin "2") (pinfunction "2_2") (pintype "passive"))
      (node (ref "C18") (pin "2") (pinfunction "2_2") (pintype "passive"))
      (node (ref "C19") (pin "2") (pinfunction "2_2") (pintype "passive"))
      (node (ref "C2") (pin "1") (pinfunction "1_1") (pintype "passive"))
      (node (ref "C3") (pin "1") (pinfunction "1_1") (pintype "passive"))
      (node (ref "C4") (pin "2") (pinfunction "2_2") (pintype "passive"))
      (node (ref "C5") (pin "2") (pinfunction "2_2") (pintype "passive"))
      (node (ref "C6") (pin "2") (pinfunction "2_2") (pintype "passive"))
      (node (ref "C7") (pin "1") (pinfunction "1_1") (pintype "passive"))
      (node (ref "C8") (pin "1") (pinfunction "1_1") (pintype "passive"))
      (node (ref "C9") (pin "2") (pinfunction "2_2") (pintype "passive"))
      (node (ref "ISP1") (pin "6") (pinfunction "GND_6") (pintype "power_in"))
      (node (ref "J1") (pin "3") (pinfunction "VSS1_3") (pintype "power_in"))
      (node (ref "J1") (pin "6") (pinfunction "VSS2_6") (pintype "power_in"))
      (node (ref "J1") (pin "GP") (pinfunction "COMMON_SW_GP") (pintype "passive"))
      (node (ref "J1") (pin "GP2") (pinfunction "GND_GP2") (pintype "power_in"))
      (node (ref "J1") (pin "GP3") (pinfunction "GND_GP3") (pintype "power_in"))
      (node (ref "J1") (pin "GP4") (pinfunction "GND_GP4") (pintype "power_in"))
      (node (ref "J2") (pin "1") (pinfunction "1_1") (pintype "passive"))
      (node (ref "J2") (pin "7") (pinfunction "7_7") (pintype "passive"))
      (node (ref "J3") (pin "1") (pinfunction "1_1") (pintype "passive"))
      (node (ref "J4") (pin "A1B12") (pinfunction "GND_A1B12") (pintype "power_in"))
      (node (ref "J4") (pin "B1A12") (pinfunction "GND_B1A12") (pintype "power_in"))
      (node (ref "JP3") (pin "1") (pinfunction "1_1") (pintype "passive"))
      (node (ref "Q1") (pin "2") (pinfunction "S_2") (pintype "bidirectional"))
      (node (ref "Q3") (pin "2") (pinfunction "S_2") (pintype "bidirectional"))
      (node (ref "R10") (pin "1") (pinfunction "1_1") (pintype "passive"))
      (node (ref "R18") (pin "1") (pinfunction "1_1") (pintype "passive"))
      (node (ref "R21") (pin "1") (pinfunction "1_1") (pintype "passive"))
      (node (ref "R23") (pin "1") (pinfunction "1_1") (pintype "passive"))
      (node (ref "R31") (pin "1") (pinfunction "1_1") (pintype "passive"))
      (node (ref "R32") (pin "1") (pinfunction "1_1") (pintype "passive"))
      (node (ref "RTC1") (pin "5") (pinfunction "GND_5") (pintype "power_in"))
      (node (ref "S1") (pin "1") (pinfunction "1_1") (pintype "bidirectional"))
      (node (ref "S1") (pin "2") (pinfunction "2_2") (pintype "bidirectional"))
      (node (ref "S2") (pin "1") (pinfunction "1_1") (pintype "bidirectional"))
      (node (ref "S2") (pin "2") (pinfunction "2_2") (pintype "bidirectional"))
      (node (ref "U1") (pin "18") (pinfunction "GND_18") (pintype "power_in"))
      (node (ref "U1") (pin "28") (pinfunction "GND_28") (pintype "power_in"))
      (node (ref "U1") (pin "39") (pinfunction "GND_39") (pintype "power_in"))
      (node (ref "U1") (pin "6") (pinfunction "GND_6") (pintype "power_in"))
      (node (ref "U1") (pin "TH") (pinfunction "EXP_TH") (pintype "power_in"))
      (node (ref "U10") (pin "2") (pinfunction "GND_2") (pintype "power_in"))
      (node (ref "U11") (pin "2") (pinfunction "GND_2") (pintype "power_in"))
      (node (ref "U11") (pin "5") (pinfunction "GND_5") (pintype "power_in"))
      (node (ref "U12") (pin "1") (pinfunction "GND_1") (pintype "power_in"))
      (node (ref "U12") (pin "7") (pinfunction "GND_7") (pintype "power_in"))
      (node (ref "U13") (pin "2") (pinfunction "GND_2") (pintype "bidirectional"))
      (node (ref "U14") (pin "2") (pinfunction "VSS_2") (pintype "passive"))
      (node (ref "U14") (pin "6") (pinfunction "VIN-_6") (pintype "input"))
      (node (ref "U2") (pin "13") (pinfunction "GND_13") (pintype "bidirectional"))
      (node (ref "U2") (pin "3") (pinfunction "GND_3") (pintype "bidirectional"))
      (node (ref "U2") (pin "6") (pinfunction "CTS#_6") (pintype "bidirectional"))
      (node (ref "U2") (pin "EP") (pinfunction "GND_EP") (pintype "bidirectional"))
      (node (ref "U3") (pin "2") (pinfunction "GND_2") (pintype "power_in"))
      (node (ref "U4") (pin "2") (pinfunction "GND_2") (pintype "power_in"))
      (node (ref "U5") (pin "4") (pinfunction "GND_4") (pintype "power_in"))
      (node (ref "U6") (pin "2") (pinfunction "GND_2") (pintype "bidirectional"))
      (node (ref "U7") (pin "2") (pinfunction "GND_2") (pintype "power_in"))
      (node (ref "U8") (pin "B1") (pinfunction "GND_B1") (pintype "power_in"))
      (node (ref "U9") (pin "2") (pinfunction "GND_2") (pintype "power_in"))
    )
    (net (code "15") (name "GPIO_EXT_D0") (class "Default")
      (node (ref "J2") (pin "6") (pinfunction "6_6") (pintype "passive"))
      (node (ref "U1") (pin "43") (pinfunction "(PCINT11/OC0A/AIN1)PB3_43") (pintype "bidirectional"))
    )
    (net (code "16") (name "GREEN_AUX_LED") (class "Default")
      (node (ref "R6") (pin "2") (pinfunction "2_2") (pintype "passive"))
      (node (ref "U1") (pin "23") (pinfunction "(PCINT20/TDO)PC4_23") (pintype "output"))
    )
    (net (code "17") (name "GREEN_STAT_LED") (class "Default")
      (node (ref "R12") (pin "1") (pinfunction "1_1") (pintype "passive"))
      (node (ref "U1") (pin "16") (pinfunction "(PCINT31/OC2A)PD7_16") (pintype "bidirectional"))
    )
    (net (code "18") (name "LOG_INT") (class "Default")
      (node (ref "R14") (pin "1") (pinfunction "1_1") (pintype "passive"))
      (node (ref "S2") (pin "3") (pinfunction "4_3") (pintype "bidirectional"))
      (node (ref "S2") (pin "4") (pinfunction "3_4") (pintype "bidirectional"))
      (node (ref "U1") (pin "33") (pinfunction "(PCINT4/ADC4)PA4_33") (pintype "bidirectional"))
    )
    (net (code "19") (name "MISO") (class "Default")
      (node (ref "ISP1") (pin "1") (pinfunction "MISO_1") (pintype "input"))
      (node (ref "J1") (pin "7") (pinfunction "DATA_OUT_7") (pintype "output"))
      (node (ref "U1") (pin "2") (pinfunction "(PCINT14/MISO)PB6_2") (pintype "bidirectional"))
    )
    (net (code "20") (name "MOSI") (class "Default")
      (node (ref "ISP1") (pin "4") (pinfunction "MOSI_4") (pintype "output"))
      (node (ref "U1") (pin "1") (pinfunction "(PCINT13/MOSI)PB5_1") (pintype "bidirectional"))
      (node (ref "U5") (pin "3") (pinfunction "2A_3") (pintype "input"))
    )
    (net (code "21") (name "MOSI_BUF") (class "Default")
      (node (ref "J1") (pin "2") (pinfunction "DATA_IN_2") (pintype "input"))
      (node (ref "U5") (pin "5") (pinfunction "2Y_5") (pintype "output"))
    )
    (net (code "22") (name "Net-(D2-BLUE_CATH)") (class "Default")
      (node (ref "D2") (pin "3") (pinfunction "BLUE_CATH_3") (pintype "bidirectional"))
      (node (ref "R5") (pin "1") (pinfunction "1_1") (pintype "passive"))
    )
    (net (code "23") (name "Net-(D2-GREEN_CATH)") (class "Default")
      (node (ref "D2") (pin "4") (pinfunction "GREEN_CATH_4") (pintype "bidirectional"))
      (node (ref "R6") (pin "1") (pinfunction "1_1") (pintype "passive"))
    )
    (net (code "24") (name "Net-(D2-RED_CATH)") (class "Default")
      (node (ref "D2") (pin "1") (pinfunction "RED_CATH_1") (pintype "bidirectional"))
      (node (ref "R8") (pin "1") (pinfunction "1_1") (pintype "passive"))
    )
    (net (code "25") (name "Net-(D3-BLUE_CATH)") (class "Default")
      (node (ref "D3") (pin "3") (pinfunction "BLUE_CATH_3") (pintype "bidirectional"))
      (node (ref "R11") (pin "2") (pinfunction "2_2") (pintype "passive"))
    )
    (net (code "26") (name "Net-(D3-GREEN_CATH)") (class "Default")
      (node (ref "D3") (pin "4") (pinfunction "GREEN_CATH_4") (pintype "bidirectional"))
      (node (ref "R12") (pin "2") (pinfunction "2_2") (pintype "passive"))
    )
    (net (code "27") (name "Net-(D3-RED_CATH)") (class "Default")
      (node (ref "D3") (pin "1") (pinfunction "RED_CATH_1") (pintype "bidirectional"))
      (node (ref "R13") (pin "2") (pinfunction "2_2") (pintype "passive"))
    )
    (net (code "28") (name "Net-(JP3-Pad2)") (class "Default")
      (node (ref "JP3") (pin "2") (pinfunction "2_2") (pintype "passive"))
      (node (ref "R24") (pin "1") (pinfunction "1_1") (pintype "passive"))
    )
    (net (code "29") (name "Net-(Q2-G)") (class "Default")
      (node (ref "Q2") (pin "1") (pinfunction "G_1") (pintype "bidirectional"))
      (node (ref "Q3") (pin "3") (pinfunction "D_3") (pintype "bidirectional"))
      (node (ref "R19") (pin "2") (pinfunction "2_2") (pintype "passive"))
    )
    (net (code "30") (name "Net-(RTC1-VBAT)") (class "Default")
      (node (ref "BT1") (pin "POWER0") (pinfunction "+_POWER0") (pintype "power_in"))
      (node (ref "BT1") (pin "POWER1") (pinfunction "+_POWER1") (pintype "power_in"))
      (node (ref "C19") (pin "1") (pinfunction "1_1") (pintype "passive"))
      (node (ref "RTC1") (pin "6") (pinfunction "VBAT_6") (pintype "power_in"))
    )
    (net (code "31") (name "Net-(U1-XTAL1)") (class "Default")
      (node (ref "C3") (pin "2") (pinfunction "2_2") (pintype "passive"))
      (node (ref "U1") (pin "8") (pinfunction "XTAL1_8") (pintype "bidirectional"))
      (node (ref "XTAL1") (pin "OSC1") (pinfunction "1_OSC1") (pintype "passive"))
    )
    (net (code "32") (name "Net-(U1-XTAL2)") (class "Default")
      (node (ref "C2") (pin "2") (pinfunction "2_2") (pintype "passive"))
      (node (ref "U1") (pin "7") (pinfunction "XTAL2_7") (pintype "bidirectional"))
      (node (ref "XTAL1") (pin "OSC2") (pinfunction "2_OSC2") (pintype "passive"))
    )
    (net (code "33") (name "Net-(U2-RXD)") (class "Default")
      (node (ref "R9") (pin "2") (pinfunction "2_2") (pintype "passive"))
      (node (ref "U2") (pin "1") (pinfunction "RXD_1") (pintype "bidirectional"))
    )
    (net (code "34") (name "Net-(U2-TXD)") (class "Default")
      (node (ref "R7") (pin "2") (pinfunction "2_2") (pintype "passive"))
      (node (ref "U2") (pin "17") (pinfunction "TXD_17") (pintype "bidirectional"))
    )
    (net (code "35") (name "Net-(U2-USBDM)") (class "Default")
      (node (ref "R3") (pin "1") (pinfunction "1_1") (pintype "passive"))
      (node (ref "U2") (pin "9") (pinfunction "USBDM_9") (pintype "bidirectional"))
    )
    (net (code "36") (name "Net-(U2-USBDP)") (class "Default")
      (node (ref "R4") (pin "1") (pinfunction "1_1") (pintype "passive"))
      (node (ref "U2") (pin "8") (pinfunction "USBDP_8") (pintype "bidirectional"))
    )
    (net (code "37") (name "Net-(U2-VCC)") (class "Default")
      (node (ref "D1") (pin "C") (pinfunction "C_C") (pintype "passive"))
      (node (ref "U2") (pin "12") (pinfunction "VCC_12") (pintype "bidirectional"))
    )
    (net (code "38") (name "Net-(U3-DELAY)") (class "Default")
      (node (ref "R10") (pin "2") (pinfunction "2_2") (pintype "passive"))
      (node (ref "U3") (pin "3") (pinfunction "DELAY_3") (pintype "input"))
    )
    (net (code "39") (name "Net-(U10-IN-)") (class "Default")
      (node (ref "R17") (pin "1") (pinfunction "1_1") (pintype "passive"))
      (node (ref "R18") (pin "2") (pinfunction "2_2") (pintype "passive"))
      (node (ref "U10") (pin "3") (pinfunction "IN-_3") (pintype "input"))
    )
    (net (code "40") (name "Net-(U10-OUT)") (class "Default")
      (node (ref "U10") (pin "4") (pinfunction "OUT_4") (pintype "output"))
      (node (ref "U9") (pin "1") (pinfunction "EN_1") (pintype "bidirectional"))
    )
    (net (code "41") (name "Net-(U11-VIN)") (class "Default")
      (node (ref "JP2") (pin "2") (pinfunction "2_2") (pintype "passive"))
      (node (ref "U11") (pin "4") (pinfunction "VIN_4") (pintype "power_in"))
    )
    (net (code "42") (name "Net-(U13-FILT)") (class "Default")
      (node (ref "C17") (pin "1") (pinfunction "1_1") (pintype "passive"))
      (node (ref "U13") (pin "1") (pinfunction "FILT_1") (pintype "bidirectional"))
    )
    (net (code "43") (name "PG") (class "Default")
      (node (ref "R20") (pin "1") (pinfunction "1_1") (pintype "passive"))
      (node (ref "U1") (pin "21") (pinfunction "(PCINT18/TCK)PC2_21") (pintype "output"))
      (node (ref "U6") (pin "1") (pinfunction "PG_1") (pintype "bidirectional"))
    )
    (net (code "44") (name "RED_STAT_LED") (class "Default")
      (node (ref "R13") (pin "1") (pinfunction "1_1") (pintype "passive"))
      (node (ref "U1") (pin "14") (pinfunction "(PCINT29/OC1A)PD5_14") (pintype "bidirectional"))
    )
    (net (code "45") (name "RST") (class "Default")
      (node (ref "C1") (pin "2") (pinfunction "2_2") (pintype "passive"))
      (node (ref "ISP1") (pin "5") (pinfunction "RST_5") (pintype "output"))
      (node (ref "R2") (pin "1") (pinfunction "1_1") (pintype "passive"))
      (node (ref "S1") (pin "3") (pinfunction "4_3") (pintype "bidirectional"))
      (node (ref "S1") (pin "4") (pinfunction "3_4") (pintype "bidirectional"))
      (node (ref "U1") (pin "4") (pinfunction "RESET_4") (pintype "input"))
      (node (ref "U3") (pin "6") (pinfunction "RSTN_6") (pintype "output"))
    )
    (net (code "46") (name "RTC_INT") (class "Default")
      (node (ref "RTC1") (pin "3") (pinfunction "SQW_3") (pintype "output"))
      (node (ref "U1") (pin "42") (pinfunction "(PCINT10/INT2/AIN0)PB2_42") (pintype "bidirectional"))
    )
    (net (code "47") (name "RX") (class "Default")
      (node (ref "R7") (pin "1") (pinfunction "1_1") (pintype "passive"))
      (node (ref "U1") (pin "9") (pinfunction "(PCINT24/RXD0)PD0_9") (pintype "bidirectional"))
    )
    (net (code "48") (name "RX_EXT") (class "Default")
      (node (ref "J2") (pin "4") (pinfunction "4_4") (pintype "passive"))
      (node (ref "U1") (pin "11") (pinfunction "(PCINT26/INT0)PD2_11") (pintype "bidirectional"))
    )
    (net (code "49") (name "RX_LED") (class "Default")
      (node (ref "R5") (pin "2") (pinfunction "2_2") (pintype "passive"))
      (node (ref "U2") (pin "7") (pinfunction "CBUS2_7") (pintype "bidirectional"))
    )
    (net (code "50") (name "SBU1") (class "Default")
      (node (ref "J4") (pin "A8") (pinfunction "SBU1_A8") (pintype "bidirectional"))
    )
    (net (code "51") (name "SBU2") (class "Default")
      (node (ref "J4") (pin "B8") (pinfunction "SBU2_B8") (pintype "bidirectional"))
    )
    (net (code "52") (name "SCK") (class "Default")
      (node (ref "ISP1") (pin "3") (pinfunction "SCK_3") (pintype "output"))
      (node (ref "U1") (pin "3") (pinfunction "(PCINT15/SCK)PB7_3") (pintype "bidirectional"))
      (node (ref "U5") (pin "1") (pinfunction "1A_1") (pintype "input"))
    )
    (net (code "53") (name "SCK_BUF") (class "Default")
      (node (ref "J1") (pin "5") (pinfunction "SCLK_5") (pintype "input"))
      (node (ref "U5") (pin "7") (pinfunction "1Y_7") (pintype "output"))
    )
    (net (code "54") (name "SCL") (class "Default")
      (node (ref "J2") (pin "10") (pinfunction "10_10") (pintype "passive"))
      (node (ref "R16") (pin "1") (pinfunction "1_1") (pintype "passive"))
      (node (ref "RTC1") (pin "8") (pinfunction "SCL_8") (pintype "bidirectional"))
      (node (ref "U1") (pin "19") (pinfunction "(PCINT16/SCL)PC0_19") (pintype "output"))
      (node (ref "U12") (pin "4") (pinfunction "SCK_4") (pintype "bidirectional"))
      (node (ref "U14") (pin "3") (pinfunction "SCL_3") (pintype "bidirectional"))
    )
    (net (code "55") (name "SDA") (class "Default")
      (node (ref "R15") (pin "1") (pinfunction "1_1") (pintype "passive"))
      (node (ref "U1") (pin "20") (pinfunction "(PCINT17/SDA)PC1_20") (pintype "output"))
      (node (ref "U4") (pin "4") (pinfunction "A_4") (pintype "bidirectional"))
    )
    (net (code "56") (name "SDA_CTRL") (class "Default")
      (node (ref "U1") (pin "24") (pinfunction "(PCINT21/TDI)PC5_24") (pintype "output"))
      (node (ref "U4") (pin "6") (pinfunction "S_6") (pintype "input"))
    )
    (net (code "57") (name "SDA_EXT") (class "Default")
      (node (ref "J2") (pin "9") (pinfunction "9_9") (pintype "passive"))
      (node (ref "JP1") (pin "2") (pinfunction "2_2") (pintype "passive"))
      (node (ref "U4") (pin "1") (pinfunction "B2_1") (pintype "bidirectional"))
    )
    (net (code "58") (name "SDA_OB") (class "Default")
      (node (ref "JP1") (pin "1") (pinfunction "1_1") (pintype "passive"))
      (node (ref "RTC1") (pin "7") (pinfunction "SDA_7") (pintype "bidirectional"))
      (node (ref "U12") (pin "3") (pinfunction "SDI_3") (pintype "bidirectional"))
      (node (ref "U14") (pin "4") (pinfunction "SDA_4") (pintype "bidirectional"))
      (node (ref "U4") (pin "3") (pinfunction "B1_3") (pintype "bidirectional"))
    )
    (net (code "59") (name "SD_CD") (class "Default")
      (node (ref "J1") (pin "CD") (pinfunction "CARD_DETECT_CD") (pintype "passive"))
      (node (ref "R1") (pin "1") (pinfunction "1_1") (pintype "passive"))
      (node (ref "U1") (pin "41") (pinfunction "(PCINT9/CLKO/T1)PB1_41") (pintype "bidirectional"))
    )
    (net (code "60") (name "SD_CS") (class "Default")
      (node (ref "U1") (pin "44") (pinfunction "(PCINT12/OC0B/~{SS})PB4_44") (pintype "bidirectional"))
      (node (ref "U5") (pin "6") (pinfunction "3A_6") (pintype "input"))
    )
    (net (code "61") (name "SD_CS_BUF") (class "Default")
      (node (ref "J1") (pin "1") (pinfunction "CS_1") (pintype "input"))
      (node (ref "U5") (pin "2") (pinfunction "3Y_2") (pintype "output"))
    )
    (net (code "62") (name "THERM_SENSE") (class "Default")
      (node (ref "U1") (pin "36") (pinfunction "(PCINT1/ADC1)PA1_36") (pintype "bidirectional"))
    )
    (net (code "63") (name "TX") (class "Default")
      (node (ref "R9") (pin "1") (pinfunction "1_1") (pintype "passive"))
      (node (ref "U1") (pin "10") (pinfunction "(PCINT25/TXD0)PD1_10") (pintype "bidirectional"))
    )
    (net (code "64") (name "TX_EXT") (class "Default")
      (node (ref "J2") (pin "3") (pinfunction "3_3") (pintype "passive"))
      (node (ref "U1") (pin "12") (pinfunction "(PCINT27/INT1)PD3_12") (pintype "bidirectional"))
    )
    (net (code "65") (name "TX_LED") (class "Default")
      (node (ref "R8") (pin "2") (pinfunction "2_2") (pintype "passive"))
      (node (ref "U2") (pin "14") (pinfunction "CBUS1_14") (pintype "bidirectional"))
    )
    (net (code "66") (name "VBAT+") (class "Default")
      (node (ref "C12") (pin "1") (pinfunction "1_1") (pintype "passive"))
      (node (ref "J3") (pin "4") (pinfunction "4_4") (pintype "passive"))
      (node (ref "Q1") (pin "1") (pinfunction "G_1") (pintype "bidirectional"))
      (node (ref "U6") (pin "4") (pinfunction "VIN_4") (pintype "bidirectional"))
      (node (ref "U8") (pin "A2") (pinfunction "VIN_A2") (pintype "power_in"))
    )
    (net (code "67") (name "VBAT-") (class "Default")
      (node (ref "J3") (pin "3") (pinfunction "3_3") (pintype "passive"))
      (node (ref "Q1") (pin "3") (pinfunction "D_3") (pintype "bidirectional"))
    )
    (net (code "68") (name "VBAT_SW") (class "Default")
      (node (ref "C10") (pin "1") (pinfunction "1_1") (pintype "passive"))
      (node (ref "R17") (pin "2") (pinfunction "2_2") (pintype "passive"))
      (node (ref "R22") (pin "2") (pinfunction "2_2") (pintype "passive"))
      (node (ref "U8") (pin "A1") (pinfunction "VOUT_A1") (pintype "power_in"))
      (node (ref "U9") (pin "5") (pinfunction "IN1_5") (pintype "power_in"))
    )
    (net (code "69") (name "VBAT_SW_CTRL") (class "Default")
      (node (ref "U1") (pin "22") (pinfunction "(PCINT19/TMS)PC3_22") (pintype "output"))
      (node (ref "U8") (pin "B2") (pinfunction "EN_B2") (pintype "input"))
    )
    (net (code "70") (name "VMAIN") (class "Default")
      (node (ref "C13") (pin "1") (pinfunction "1_1") (pintype "passive"))
      (node (ref "JP2") (pin "1") (pinfunction "1_1") (pintype "passive"))
      (node (ref "U7") (pin "1") (pinfunction "VIN_1") (pintype "power_in"))
      (node (ref "U9") (pin "4") (pinfunction "OUT_4") (pintype "power_in"))
    )
    (net (code "71") (name "VREF") (class "Default")
      (node (ref "C18") (pin "1") (pinfunction "1_1") (pintype "passive"))
      (node (ref "J3") (pin "6") (pinfunction "6_6") (pintype "passive"))
      (node (ref "U1") (pin "34") (pinfunction "(PCINT3/ADC3)PA3_34") (pintype "bidirectional"))
      (node (ref "U13") (pin "5") (pinfunction "OUTS_5") (pintype "bidirectional"))
      (node (ref "U13") (pin "6") (pinfunction "OUTF_6") (pintype "bidirectional"))
    )
    (net (code "72") (name "VSWITCH") (class "Default")
      (node (ref "J3") (pin "2") (pinfunction "2_2") (pintype "passive"))
      (node (ref "U11") (pin "1") (pinfunction "VOUT_1") (pintype "power_in"))
    )
    (net (code "73") (name "VSWITCH_CTRL") (class "Default")
      (node (ref "U1") (pin "13") (pinfunction "(PCINT28/OC1B)PD4_13") (pintype "bidirectional"))
      (node (ref "U11") (pin "6") (pinfunction "EN_6") (pintype "input"))
    )
    (net (code "74") (name "VUSB") (class "Default")
      (node (ref "C11") (pin "1") (pinfunction "1_1") (pintype "passive"))
      (node (ref "C5") (pin "1") (pinfunction "1_1") (pintype "passive"))
      (node (ref "C6") (pin "1") (pinfunction "1_1") (pintype "passive"))
      (node (ref "D1") (pin "A") (pinfunction "A_A") (pintype "passive"))
      (node (ref "J4") (pin "A4B9") (pinfunction "VBUS_A4B9") (pintype "power_in"))
      (node (ref "J4") (pin "B4A9") (pinfunction "VBUS_B4A9") (pintype "power_in"))
      (node (ref "Q3") (pin "1") (pinfunction "G_1") (pintype "bidirectional"))
      (node (ref "R21") (pin "2") (pinfunction "2_2") (pintype "passive"))
      (node (ref "U9") (pin "3") (pinfunction "IN2_3") (pintype "power_in"))
    )
    (net (code "75") (name "WD_HOLD") (class "Default")
      (node (ref "U1") (pin "26") (pinfunction "(PCINT23/TOSC2)PC7_26") (pintype "output"))
      (node (ref "U3") (pin "4") (pinfunction "DONE_4") (pintype "input"))
    )
    (net (code "76") (name "unconnected-(J1-DAT1-Pad8)") (class "Default")
      (node (ref "J1") (pin "8") (pinfunction "DAT1_8") (pintype "bidirectional"))
    )
    (net (code "77") (name "unconnected-(J1-DAT2-Pad9)") (class "Default")
      (node (ref "J1") (pin "9") (pinfunction "DAT2_9") (pintype "bidirectional"))
    )
    (net (code "78") (name "unconnected-(J1-WRITE_PROTECT-PadWP)") (class "Default")
      (node (ref "J1") (pin "WP") (pinfunction "WRITE_PROTECT_WP") (pintype "passive"))
    )
    (net (code "79") (name "unconnected-(RTC1-32KHZ-Pad1)") (class "Default")
      (node (ref "RTC1") (pin "1") (pinfunction "32KHZ_1") (pintype "output"))
    )
    (net (code "80") (name "unconnected-(RTC1-RST-Pad4)") (class "Default")
      (node (ref "RTC1") (pin "4") (pinfunction "RST_4") (pintype "bidirectional"))
    )
    (net (code "81") (name "unconnected-(U1-(PCINT5{slash}ADC5)PA5-Pad32)") (class "Default")
      (node (ref "U1") (pin "32") (pinfunction "(PCINT5/ADC5)PA5_32") (pintype "bidirectional"))
    )
    (net (code "82") (name "unconnected-(U1-(PCINT6{slash}ADC6)PA6-Pad31)") (class "Default")
      (node (ref "U1") (pin "31") (pinfunction "(PCINT6/ADC6)PA6_31") (pintype "bidirectional"))
    )
    (net (code "83") (name "unconnected-(U1-(PCINT7{slash}ADC7)PA7-Pad30)") (class "Default")
      (node (ref "U1") (pin "30") (pinfunction "(PCINT7/ADC7)PA7_30") (pintype "bidirectional"))
    )
    (net (code "84") (name "unconnected-(U1-(PCINT8{slash}XCK0{slash}T0)PB0-Pad40)") (class "Default")
      (node (ref "U1") (pin "40") (pinfunction "(PCINT8/XCK0/T0)PB0_40") (pintype "bidirectional"))
    )
    (net (code "85") (name "unconnected-(U2-CBUS0-Pad15)") (class "Default")
      (node (ref "U2") (pin "15") (pinfunction "CBUS0_15") (pintype "bidirectional"))
    )
    (net (code "86") (name "unconnected-(U2-CBUS3-Pad16)") (class "Default")
      (node (ref "U2") (pin "16") (pinfunction "CBUS3_16") (pintype "bidirectional"))
    )
    (net (code "87") (name "unconnected-(U2-DCD#-Pad5)") (class "Default")
      (node (ref "U2") (pin "5") (pinfunction "DCD#_5") (pintype "bidirectional"))
    )
    (net (code "88") (name "unconnected-(U2-DSR#-Pad4)") (class "Default")
      (node (ref "U2") (pin "4") (pinfunction "DSR#_4") (pintype "bidirectional"))
    )
    (net (code "89") (name "unconnected-(U2-RI#-Pad2)") (class "Default")
      (node (ref "U2") (pin "2") (pinfunction "RI#_2") (pintype "bidirectional"))
    )
    (net (code "90") (name "unconnected-(U2-RTS#-Pad19)") (class "Default")
      (node (ref "U2") (pin "19") (pinfunction "RTS#_19") (pintype "bidirectional"))
    )
    (net (code "91") (name "unconnected-(U3-WAKE-Pad5)") (class "Default")
      (node (ref "U3") (pin "5") (pinfunction "WAKE_5") (pintype "output"))
    )
  )
)
